# Maiskolben_THT.net
KiCad netlist of a schematic drawn in EAGLE
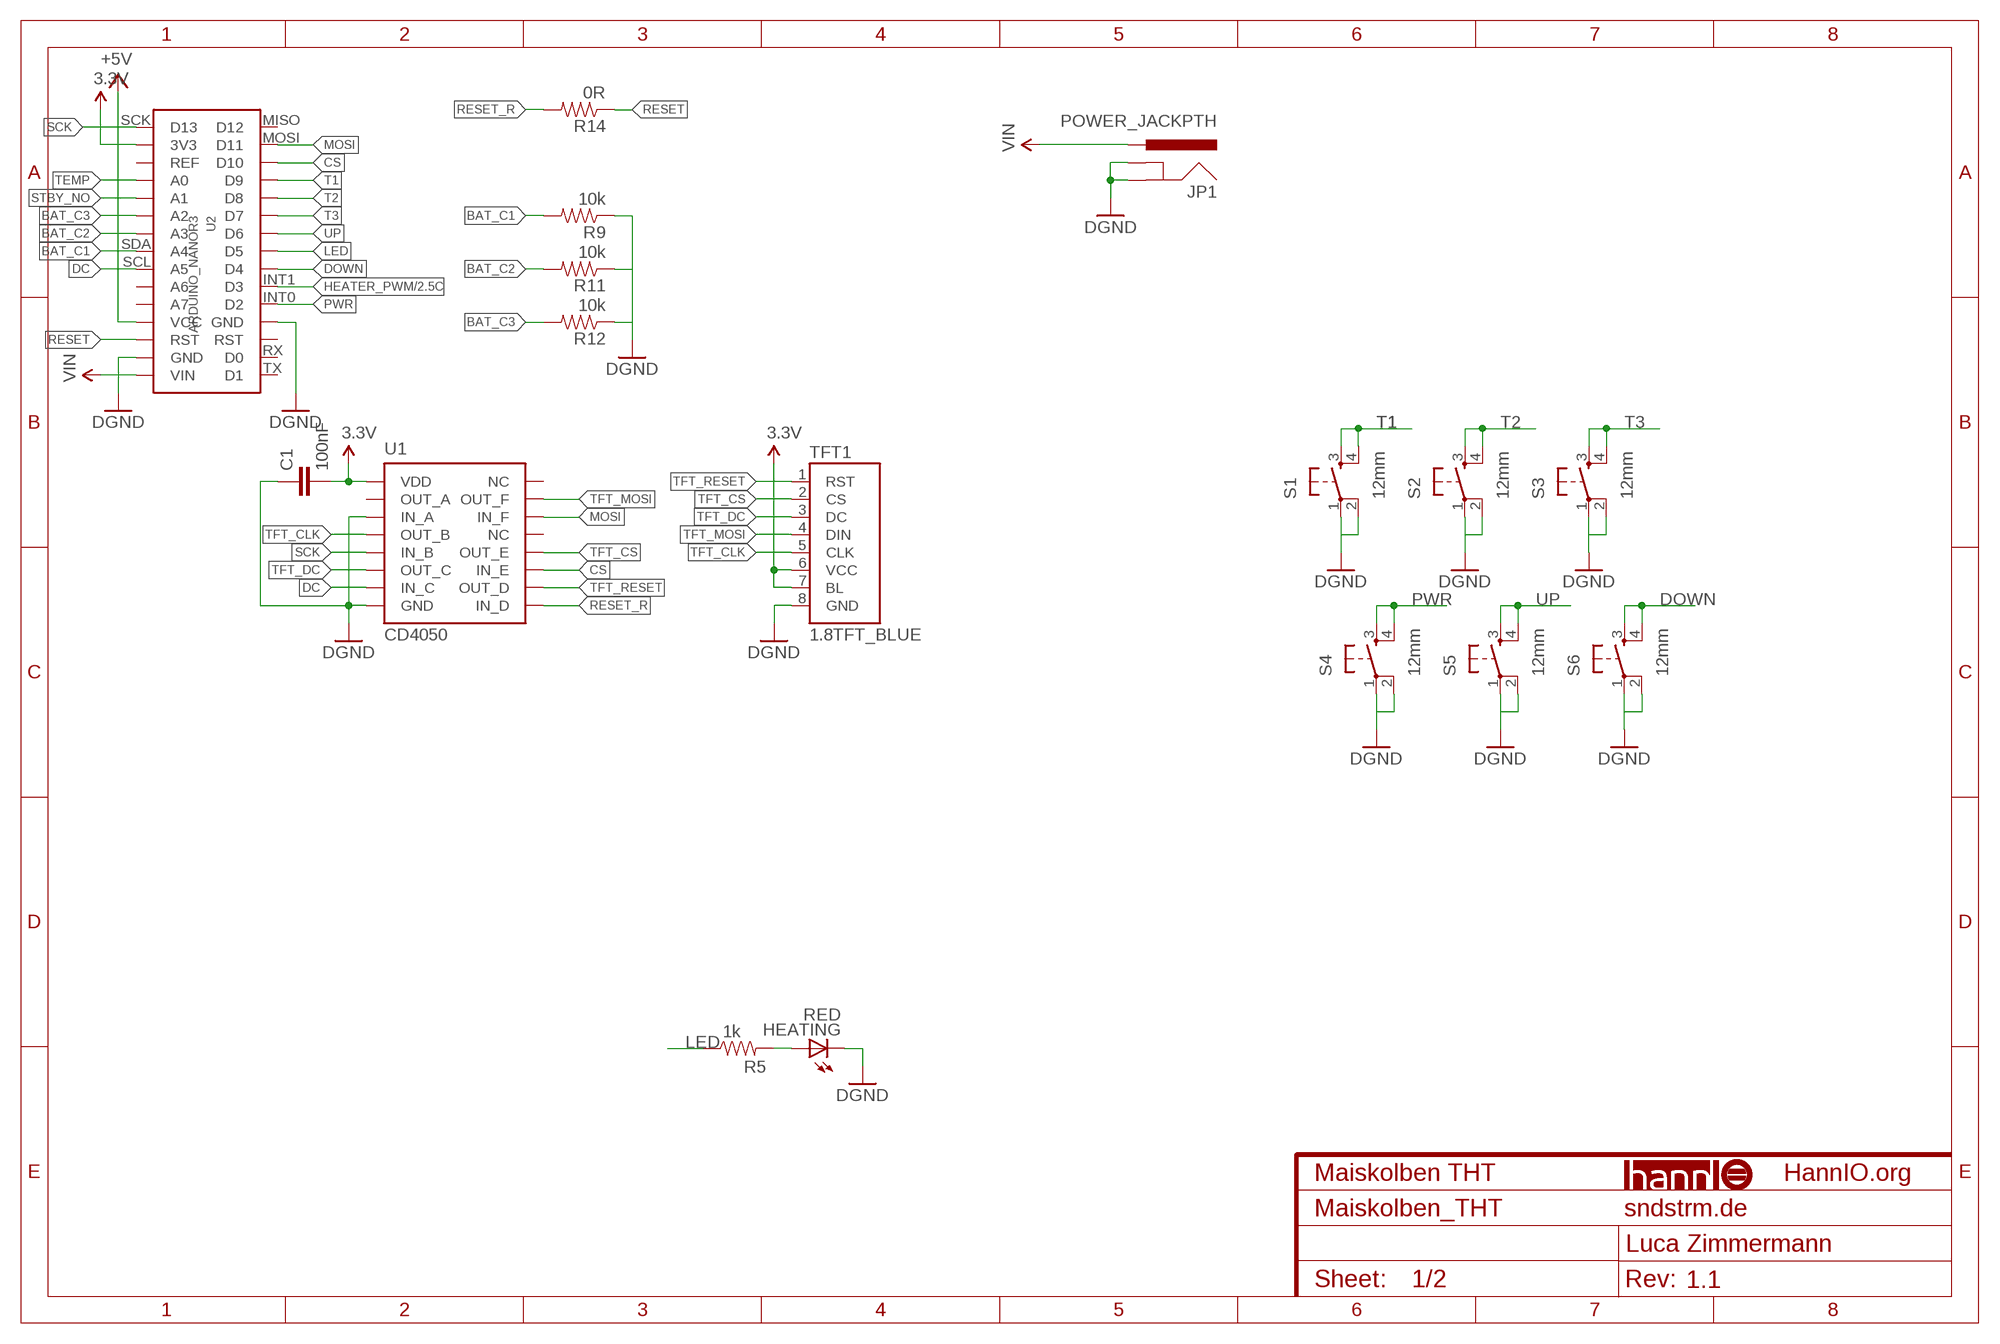
[diagram p0: schematic, sheet 1]
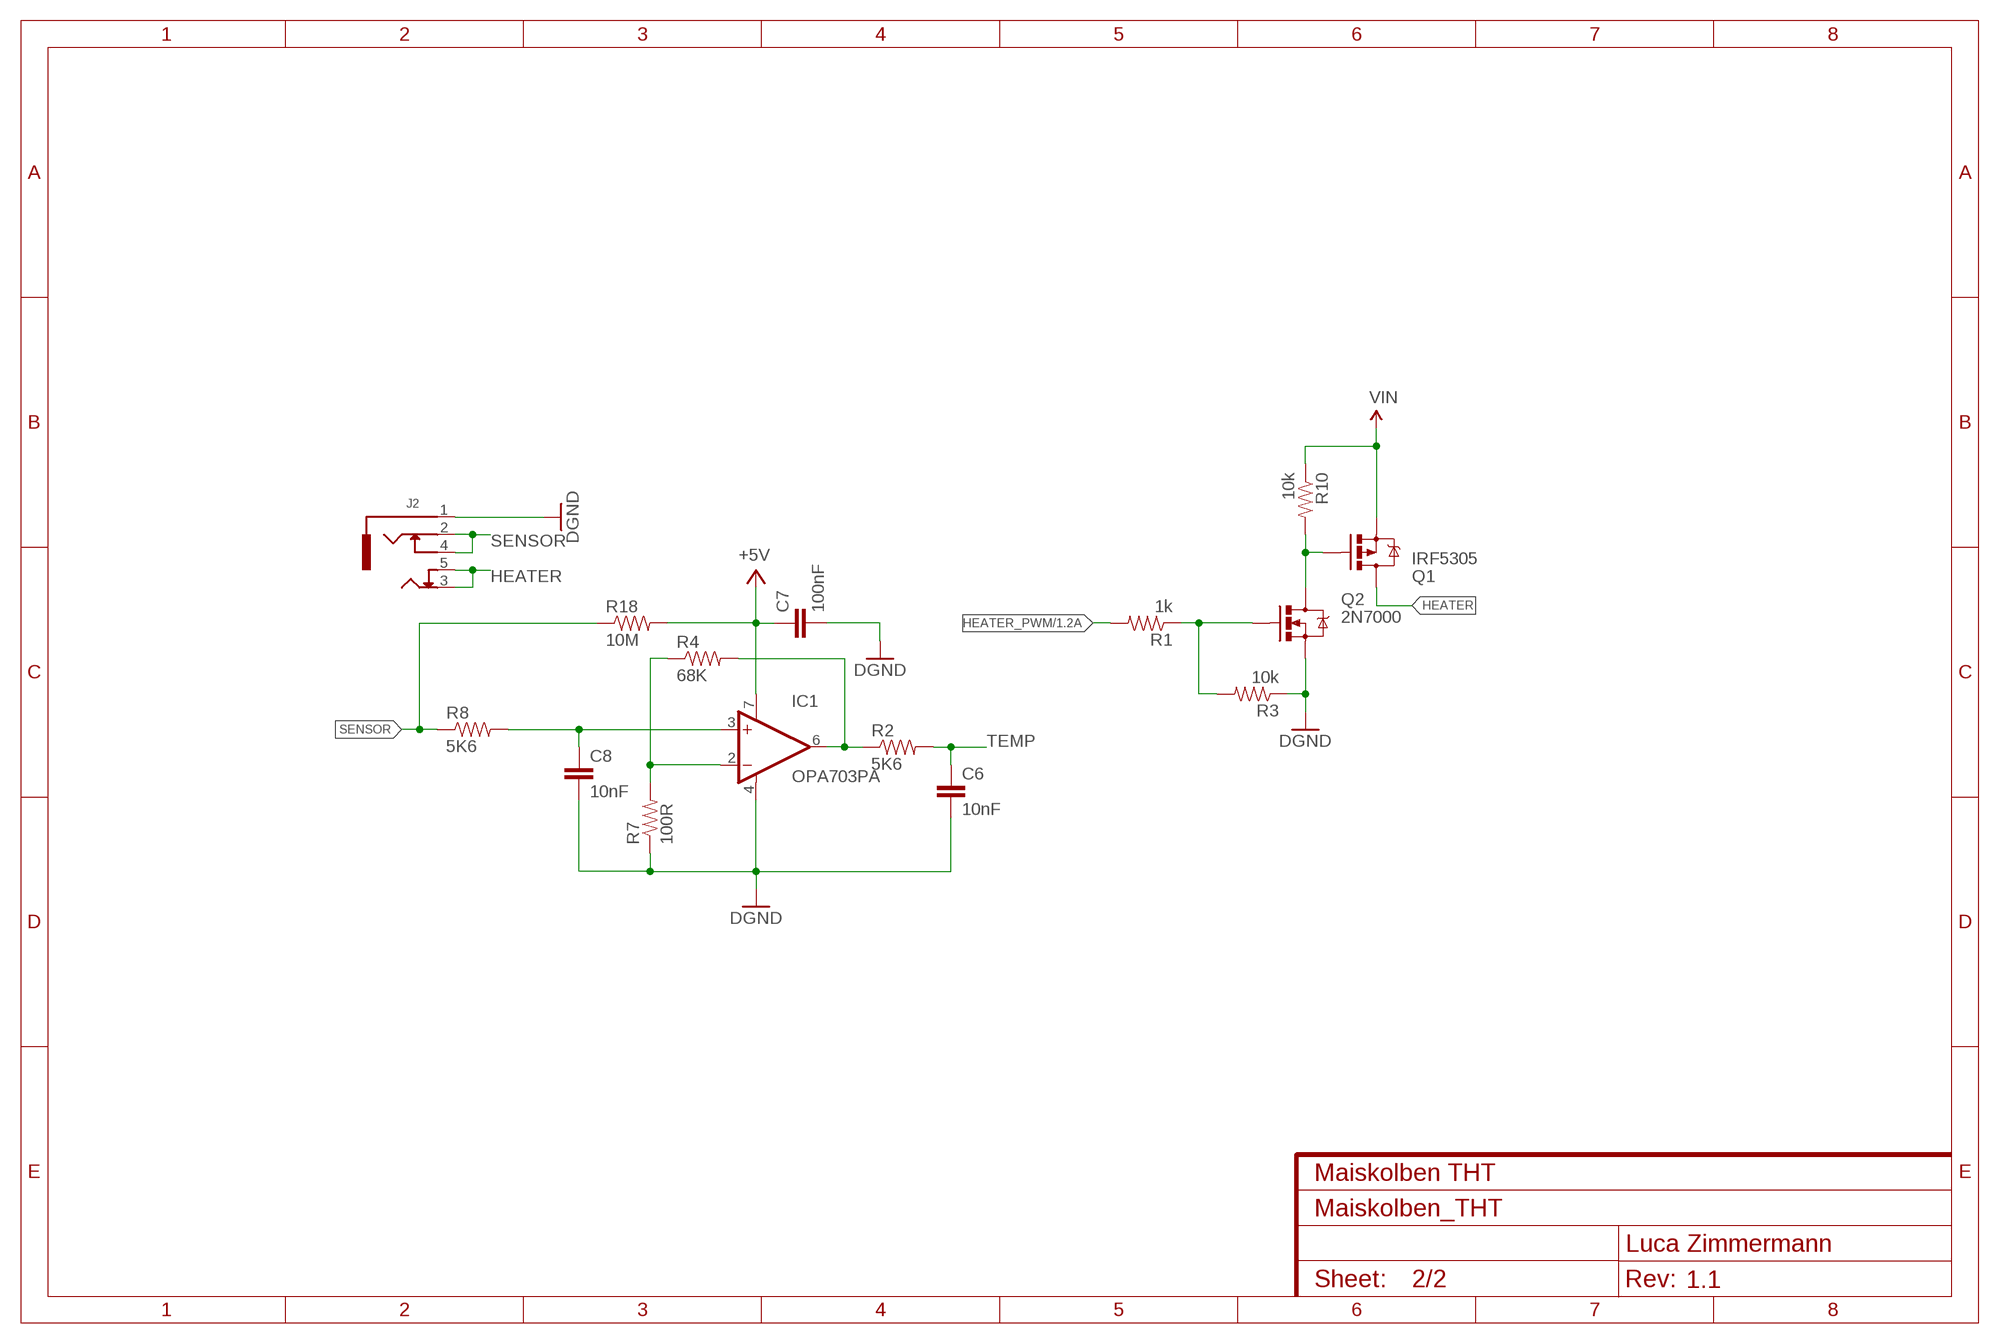
[diagram p1: schematic, sheet 2]

(export (version "E")
  (design (tool "Eeschema 10.0.6"))
  (components
    (comp (ref "C6")
      (value "10nF")
      (footprint "eagle-import:CAP-PTH-SMALLEZ")
      (libsource (lib "eagle-import") (part "CAPEZ"))
    )
    (comp (ref "C7")
      (value "100nF")
      (footprint "eagle-import:CAP-PTH-SMALLEZ")
      (libsource (lib "eagle-import") (part "CAPEZ"))
    )
    (comp (ref "C8")
      (value "10nF")
      (footprint "eagle-import:CAP-PTH-SMALLEZ")
      (libsource (lib "eagle-import") (part "CAPEZ"))
    )
    (comp (ref "IC1")
      (value "OPA703PA")
      (footprint "eagle-import:DIL08")
      (fields (field (name "MPN") "OPA340PA"))
      (libsource (lib "eagle-import") (part "OPA340P"))
    )
    (comp (ref "J2")
      (value "AUDIO_JACK_5PEBS_35")
      (footprint "eagle-import:EBS_35")
      (libsource (lib "eagle-import") (part "AUDIO_JACK_5PEBS_35"))
    )
    (comp (ref "Q1")
      (value "IRF5305")
      (footprint "eagle-import:TO220V")
      (libsource (lib "eagle-import") (part "MOSFET-PCHANNELFQP27P06"))
    )
    (comp (ref "Q2")
      (value "2N7000")
      (footprint "eagle-import:TO-92")
      (libsource (lib "eagle-import") (part "MOSFET-NCHANNEL2N7000"))
    )
    (comp (ref "R1")
      (value "1k")
      (footprint "eagle-import:AXIAL-0.3")
      (libsource (lib "eagle-import") (part "RESISTORAXIAL-0.3"))
    )
    (comp (ref "R2")
      (value "5K6")
      (footprint "eagle-import:AXIAL-0.3")
      (libsource (lib "eagle-import") (part "RESISTORAXIAL-0.3"))
    )
    (comp (ref "R3")
      (value "10k")
      (footprint "eagle-import:AXIAL-0.3")
      (libsource (lib "eagle-import") (part "RESISTORAXIAL-0.3"))
    )
    (comp (ref "R4")
      (value "68K")
      (footprint "eagle-import:AXIAL-0.3")
      (libsource (lib "eagle-import") (part "RESISTORAXIAL-0.3"))
    )
    (comp (ref "R7")
      (value "100R")
      (footprint "eagle-import:AXIAL-0.3")
      (libsource (lib "eagle-import") (part "RESISTORAXIAL-0.3"))
    )
    (comp (ref "R8")
      (value "5K6")
      (footprint "eagle-import:AXIAL-0.3")
      (libsource (lib "eagle-import") (part "RESISTORAXIAL-0.3"))
    )
    (comp (ref "R10")
      (value "10k")
      (footprint "eagle-import:AXIAL-0.3")
      (libsource (lib "eagle-import") (part "RESISTORAXIAL-0.3"))
    )
    (comp (ref "R18")
      (value "10M")
      (footprint "eagle-import:AXIAL-0.3")
      (libsource (lib "eagle-import") (part "RESISTORAXIAL-0.3"))
    )
    (comp (ref "C1")
      (value "100nF")
      (footprint "eagle-import:CAP-PTH-SMALLEZ")
      (libsource (lib "eagle-import") (part "CAPEZ"))
    )
    (comp (ref "HEATING")
      (value "RED")
      (footprint "eagle-import:LED5MM")
      (libsource (lib "eagle-import") (part "LED5MM"))
    )
    (comp (ref "JP1")
      (value "POWER_JACKPTH")
      (footprint "eagle-import:POWER_JACK_PTH")
      (libsource (lib "eagle-import") (part "POWER_JACKPTH"))
    )
    (comp (ref "R5")
      (value "1k")
      (footprint "eagle-import:AXIAL-0.3")
      (libsource (lib "eagle-import") (part "RESISTORAXIAL-0.3"))
    )
    (comp (ref "R9")
      (value "10k")
      (footprint "eagle-import:AXIAL-0.3")
      (libsource (lib "eagle-import") (part "RESISTORAXIAL-0.3"))
    )
    (comp (ref "R11")
      (value "10k")
      (footprint "eagle-import:AXIAL-0.3")
      (libsource (lib "eagle-import") (part "RESISTORAXIAL-0.3"))
    )
    (comp (ref "R12")
      (value "10k")
      (footprint "eagle-import:AXIAL-0.3")
      (libsource (lib "eagle-import") (part "RESISTORAXIAL-0.3"))
    )
    (comp (ref "R14")
      (value "0R")
      (footprint "eagle-import:AXIAL-0.3")
      (libsource (lib "eagle-import") (part "RESISTORAXIAL-0.3"))
    )
    (comp (ref "S1")
      (value "12mm")
      (footprint "eagle-import:TACTILE-PTH")
      (libsource (lib "eagle-import") (part "TAC_SWITCHPTH"))
    )
    (comp (ref "S2")
      (value "12mm")
      (footprint "eagle-import:TACTILE-PTH")
      (libsource (lib "eagle-import") (part "TAC_SWITCHPTH"))
    )
    (comp (ref "S3")
      (value "12mm")
      (footprint "eagle-import:TACTILE-PTH")
      (libsource (lib "eagle-import") (part "TAC_SWITCHPTH"))
    )
    (comp (ref "S4")
      (value "12mm")
      (footprint "eagle-import:TACTILE-PTH")
      (libsource (lib "eagle-import") (part "TAC_SWITCHPTH"))
    )
    (comp (ref "S5")
      (value "12mm")
      (footprint "eagle-import:TACTILE-PTH")
      (libsource (lib "eagle-import") (part "TAC_SWITCHPTH"))
    )
    (comp (ref "S6")
      (value "12mm")
      (footprint "eagle-import:TACTILE-PTH")
      (libsource (lib "eagle-import") (part "TAC_SWITCHPTH"))
    )
    (comp (ref "TFT1")
      (value "1.8TFT_BLUE")
      (footprint "eagle-import:1.8TFT_BLUE")
      (libsource (lib "eagle-import") (part "1.8TFT_BLUE"))
    )
    (comp (ref "U$1")
      (value "HANNIO_MEDIUM")
      (footprint "eagle-import:HANNIO_MEDIUM")
      (libsource (lib "eagle-import") (part "HANNIO_MEDIUM"))
    )
    (comp (ref "U1")
      (value "CD4050DIP16")
      (footprint "eagle-import:CD4050")
      (libsource (lib "eagle-import") (part "CD4050DIP16"))
    )
    (comp (ref "U2")
      (value "ARDUINO_NANOR3")
      (footprint "eagle-import:ARDUINO-NANO")
      (libsource (lib "eagle-import") (part "ARDUINO_NANOR3"))
    )
  )
  (nets
    (net (code "1") (name "+5V") (class "Default")
      (node (ref "C7") (pin "1") (pinfunction "1_1") (pintype "passive"))
      (node (ref "IC1") (pin "7") (pinfunction "V+_7") (pintype "power_in"))
      (node (ref "R18") (pin "P$2") (pinfunction "2_P$2") (pintype "passive"))
      (node (ref "U2") (pin "VCC") (pinfunction "VCC_VCC") (pintype "power_in"))
    )
    (net (code "2") (name "3.3V") (class "Default")
      (node (ref "C1") (pin "2") (pinfunction "2_2") (pintype "passive"))
      (node (ref "TFT1") (pin "6") (pinfunction "VCC_6") (pintype "power_in"))
      (node (ref "TFT1") (pin "7") (pinfunction "BL_7") (pintype "passive"))
      (node (ref "U1") (pin "VDD") (pinfunction "VDD_VDD") (pintype "power_in"))
      (node (ref "U2") (pin "3V3") (pinfunction "3V3_3V3") (pintype "power_in"))
    )
    (net (code "3") (name "BAT_C1") (class "Default")
      (node (ref "R9") (pin "P$2") (pinfunction "2_P$2") (pintype "passive"))
      (node (ref "U2") (pin "SDA") (pinfunction "A4_SDA") (pintype "bidirectional"))
    )
    (net (code "4") (name "BAT_C2") (class "Default")
      (node (ref "R11") (pin "P$2") (pinfunction "2_P$2") (pintype "passive"))
      (node (ref "U2") (pin "A3") (pinfunction "A3_A3") (pintype "bidirectional"))
    )
    (net (code "5") (name "BAT_C3") (class "Default")
      (node (ref "R12") (pin "P$2") (pinfunction "2_P$2") (pintype "passive"))
      (node (ref "U2") (pin "A2") (pinfunction "A2_A2") (pintype "bidirectional"))
    )
    (net (code "6") (name "CS") (class "Default")
      (node (ref "U1") (pin "IN_E") (pinfunction "IN_E_IN_E") (pintype "bidirectional"))
      (node (ref "U2") (pin "D10") (pinfunction "D10_D10") (pintype "bidirectional"))
    )
    (net (code "7") (name "DC") (class "Default")
      (node (ref "U1") (pin "IN_C") (pinfunction "IN_C_IN_C") (pintype "bidirectional"))
      (node (ref "U2") (pin "SCL") (pinfunction "A5_SCL") (pintype "bidirectional"))
    )
    (net (code "8") (name "DGND") (class "Default")
      (node (ref "C1") (pin "1") (pinfunction "1_1") (pintype "passive"))
      (node (ref "C6") (pin "2") (pinfunction "2_2") (pintype "passive"))
      (node (ref "C7") (pin "2") (pinfunction "2_2") (pintype "passive"))
      (node (ref "C8") (pin "2") (pinfunction "2_2") (pintype "passive"))
      (node (ref "HEATING") (pin "K") (pinfunction "C_K") (pintype "passive"))
      (node (ref "IC1") (pin "4") (pinfunction "V-_4") (pintype "power_in"))
      (node (ref "J2") (pin "1") (pinfunction "GND_1") (pintype "bidirectional"))
      (node (ref "JP1") (pin "GND") (pinfunction "GND_GND") (pintype "bidirectional"))
      (node (ref "JP1") (pin "GNDBREAK") (pinfunction "GNDBREAK_GNDBREAK") (pintype "bidirectional"))
      (node (ref "Q2") (pin "1") (pinfunction "S_1") (pintype "passive"))
      (node (ref "R11") (pin "P$1") (pinfunction "1_P$1") (pintype "passive"))
      (node (ref "R12") (pin "P$1") (pinfunction "1_P$1") (pintype "passive"))
      (node (ref "R3") (pin "P$1") (pinfunction "1_P$1") (pintype "passive"))
      (node (ref "R7") (pin "P$1") (pinfunction "1_P$1") (pintype "passive"))
      (node (ref "R9") (pin "P$1") (pinfunction "1_P$1") (pintype "passive"))
      (node (ref "S1") (pin "1") (pinfunction "1_1") (pintype "passive"))
      (node (ref "S1") (pin "2") (pinfunction "2_2") (pintype "passive"))
      (node (ref "S2") (pin "1") (pinfunction "1_1") (pintype "passive"))
      (node (ref "S2") (pin "2") (pinfunction "2_2") (pintype "passive"))
      (node (ref "S3") (pin "1") (pinfunction "1_1") (pintype "passive"))
      (node (ref "S3") (pin "2") (pinfunction "2_2") (pintype "passive"))
      (node (ref "S4") (pin "1") (pinfunction "1_1") (pintype "passive"))
      (node (ref "S4") (pin "2") (pinfunction "2_2") (pintype "passive"))
      (node (ref "S5") (pin "1") (pinfunction "1_1") (pintype "passive"))
      (node (ref "S5") (pin "2") (pinfunction "2_2") (pintype "passive"))
      (node (ref "S6") (pin "1") (pinfunction "1_1") (pintype "passive"))
      (node (ref "S6") (pin "2") (pinfunction "2_2") (pintype "passive"))
      (node (ref "TFT1") (pin "8") (pinfunction "GND_8") (pintype "power_in"))
      (node (ref "U1") (pin "GND") (pinfunction "GND_GND") (pintype "power_in"))
      (node (ref "U1") (pin "IN_A") (pinfunction "IN_A_IN_A") (pintype "bidirectional"))
      (node (ref "U2") (pin "GND@1") (pinfunction "GND_GND@1") (pintype "power_in"))
      (node (ref "U2") (pin "GND@2") (pinfunction "GND_GND@2") (pintype "power_in"))
    )
    (net (code "9") (name "DOWN") (class "Default")
      (node (ref "S6") (pin "3") (pinfunction "3_3") (pintype "passive"))
      (node (ref "S6") (pin "4") (pinfunction "4_4") (pintype "passive"))
      (node (ref "U2") (pin "D4") (pinfunction "D4_D4") (pintype "bidirectional"))
    )
    (net (code "10") (name "HEATER") (class "Default")
      (node (ref "J2") (pin "3") (pinfunction "TIP_3") (pintype "bidirectional"))
      (node (ref "J2") (pin "5") (pinfunction "TIP_NC_5") (pintype "bidirectional"))
      (node (ref "Q1") (pin "2") (pinfunction "D_2") (pintype "passive"))
    )
    (net (code "11") (name "HEATER_PWM") (class "Default")
      (node (ref "R1") (pin "P$2") (pinfunction "2_P$2") (pintype "passive"))
      (node (ref "U2") (pin "INT1") (pinfunction "D3_INT1") (pintype "bidirectional"))
    )
    (net (code "12") (name "LED") (class "Default")
      (node (ref "R5") (pin "P$1") (pinfunction "1_P$1") (pintype "passive"))
      (node (ref "U2") (pin "D5") (pinfunction "D5_D5") (pintype "bidirectional"))
    )
    (net (code "13") (name "MOSI") (class "Default")
      (node (ref "U1") (pin "IN_F") (pinfunction "IN_F_IN_F") (pintype "bidirectional"))
      (node (ref "U2") (pin "MOSI") (pinfunction "D11_MOSI") (pintype "bidirectional"))
    )
    (net (code "14") (name "Net-(IC1-+IN)") (class "Default")
      (node (ref "C8") (pin "1") (pinfunction "1_1") (pintype "passive"))
      (node (ref "IC1") (pin "3") (pinfunction "+IN_3") (pintype "input"))
      (node (ref "R8") (pin "P$2") (pinfunction "2_P$2") (pintype "passive"))
    )
    (net (code "15") (name "Net-(IC1--IN)") (class "Default")
      (node (ref "IC1") (pin "2") (pinfunction "-IN_2") (pintype "input"))
      (node (ref "R4") (pin "P$1") (pinfunction "1_P$1") (pintype "passive"))
      (node (ref "R7") (pin "P$2") (pinfunction "2_P$2") (pintype "passive"))
    )
    (net (code "16") (name "Net-(IC1-OUT)") (class "Default")
      (node (ref "IC1") (pin "6") (pinfunction "OUT_6") (pintype "output"))
      (node (ref "R2") (pin "P$1") (pinfunction "1_P$1") (pintype "passive"))
      (node (ref "R4") (pin "P$2") (pinfunction "2_P$2") (pintype "passive"))
    )
    (net (code "17") (name "Net-(Q1-G)") (class "Default")
      (node (ref "Q1") (pin "1") (pinfunction "G_1") (pintype "passive"))
      (node (ref "Q2") (pin "3") (pinfunction "D_3") (pintype "passive"))
      (node (ref "R10") (pin "P$2") (pinfunction "2_P$2") (pintype "passive"))
    )
    (net (code "18") (name "Net-(Q2-G)") (class "Default")
      (node (ref "Q2") (pin "2") (pinfunction "G_2") (pintype "passive"))
      (node (ref "R1") (pin "P$1") (pinfunction "1_P$1") (pintype "passive"))
      (node (ref "R3") (pin "P$2") (pinfunction "2_P$2") (pintype "passive"))
    )
    (net (code "19") (name "Net-(R5-2)") (class "Default")
      (node (ref "HEATING") (pin "A") (pinfunction "A_A") (pintype "passive"))
      (node (ref "R5") (pin "P$2") (pinfunction "2_P$2") (pintype "passive"))
    )
    (net (code "20") (name "PWR") (class "Default")
      (node (ref "S4") (pin "3") (pinfunction "3_3") (pintype "passive"))
      (node (ref "S4") (pin "4") (pinfunction "4_4") (pintype "passive"))
      (node (ref "U2") (pin "INT0") (pinfunction "D2_INT0") (pintype "bidirectional"))
    )
    (net (code "21") (name "RESET") (class "Default")
      (node (ref "R14") (pin "P$1") (pinfunction "1_P$1") (pintype "passive"))
      (node (ref "U2") (pin "RST@2") (pinfunction "RST_RST@2") (pintype "bidirectional"))
    )
    (net (code "22") (name "RESET_R") (class "Default")
      (node (ref "R14") (pin "P$2") (pinfunction "2_P$2") (pintype "passive"))
      (node (ref "U1") (pin "IN_D") (pinfunction "IN_D_IN_D") (pintype "bidirectional"))
    )
    (net (code "23") (name "SCK") (class "Default")
      (node (ref "U1") (pin "IN_B") (pinfunction "IN_B_IN_B") (pintype "bidirectional"))
      (node (ref "U2") (pin "SCK") (pinfunction "D13_SCK") (pintype "bidirectional"))
    )
    (net (code "24") (name "SENSOR") (class "Default")
      (node (ref "J2") (pin "2") (pinfunction "RING_2") (pintype "bidirectional"))
      (node (ref "J2") (pin "4") (pinfunction "RING_NC_4") (pintype "bidirectional"))
      (node (ref "R18") (pin "P$1") (pinfunction "1_P$1") (pintype "passive"))
      (node (ref "R8") (pin "P$1") (pinfunction "1_P$1") (pintype "passive"))
    )
    (net (code "25") (name "STBY_NO") (class "Default")
      (node (ref "U2") (pin "A1") (pinfunction "A1_A1") (pintype "bidirectional"))
    )
    (net (code "26") (name "T1") (class "Default")
      (node (ref "S1") (pin "3") (pinfunction "3_3") (pintype "passive"))
      (node (ref "S1") (pin "4") (pinfunction "4_4") (pintype "passive"))
      (node (ref "U2") (pin "D9") (pinfunction "D9_D9") (pintype "bidirectional"))
    )
    (net (code "27") (name "T2") (class "Default")
      (node (ref "S2") (pin "3") (pinfunction "3_3") (pintype "passive"))
      (node (ref "S2") (pin "4") (pinfunction "4_4") (pintype "passive"))
      (node (ref "U2") (pin "D8") (pinfunction "D8_D8") (pintype "bidirectional"))
    )
    (net (code "28") (name "T3") (class "Default")
      (node (ref "S3") (pin "3") (pinfunction "3_3") (pintype "passive"))
      (node (ref "S3") (pin "4") (pinfunction "4_4") (pintype "passive"))
      (node (ref "U2") (pin "D7") (pinfunction "D7_D7") (pintype "bidirectional"))
    )
    (net (code "29") (name "TEMP") (class "Default")
      (node (ref "C6") (pin "1") (pinfunction "1_1") (pintype "passive"))
      (node (ref "R2") (pin "P$2") (pinfunction "2_P$2") (pintype "passive"))
      (node (ref "U2") (pin "A0") (pinfunction "A0_A0") (pintype "bidirectional"))
    )
    (net (code "30") (name "TFT_CLK") (class "Default")
      (node (ref "TFT1") (pin "5") (pinfunction "CLK_5") (pintype "input"))
      (node (ref "U1") (pin "OUT_B") (pinfunction "OUT_B_OUT_B") (pintype "bidirectional"))
    )
    (net (code "31") (name "TFT_CS") (class "Default")
      (node (ref "TFT1") (pin "2") (pinfunction "CS_2") (pintype "input"))
      (node (ref "U1") (pin "OUT_E") (pinfunction "OUT_E_OUT_E") (pintype "bidirectional"))
    )
    (net (code "32") (name "TFT_DC") (class "Default")
      (node (ref "TFT1") (pin "3") (pinfunction "DC_3") (pintype "input"))
      (node (ref "U1") (pin "OUT_C") (pinfunction "OUT_C_OUT_C") (pintype "bidirectional"))
    )
    (net (code "33") (name "TFT_MOSI") (class "Default")
      (node (ref "TFT1") (pin "4") (pinfunction "DIN_4") (pintype "input"))
      (node (ref "U1") (pin "OUT_F") (pinfunction "OUT_F_OUT_F") (pintype "bidirectional"))
    )
    (net (code "34") (name "TFT_RESET") (class "Default")
      (node (ref "TFT1") (pin "1") (pinfunction "RST_1") (pintype "input"))
      (node (ref "U1") (pin "OUT_D") (pinfunction "OUT_D_OUT_D") (pintype "bidirectional"))
    )
    (net (code "35") (name "UP") (class "Default")
      (node (ref "S5") (pin "3") (pinfunction "3_3") (pintype "passive"))
      (node (ref "S5") (pin "4") (pinfunction "4_4") (pintype "passive"))
      (node (ref "U2") (pin "D6") (pinfunction "D6_D6") (pintype "bidirectional"))
    )
    (net (code "36") (name "VIN") (class "Default")
      (node (ref "JP1") (pin "PWR") (pinfunction "PWR_PWR") (pintype "bidirectional"))
      (node (ref "Q1") (pin "3") (pinfunction "S_3") (pintype "passive"))
      (node (ref "R10") (pin "P$1") (pinfunction "1_P$1") (pintype "passive"))
      (node (ref "U2") (pin "VIN") (pinfunction "VIN_VIN") (pintype "power_in"))
    )
    (net (code "37") (name "unconnected-(U1-NC-PadNC@1)") (class "Default")
      (node (ref "U1") (pin "NC@1") (pinfunction "NC_NC@1") (pintype "no_connect"))
    )
    (net (code "38") (name "unconnected-(U1-NC-PadNC@2)") (class "Default")
      (node (ref "U1") (pin "NC@2") (pinfunction "NC_NC@2") (pintype "no_connect"))
    )
    (net (code "39") (name "unconnected-(U1-PadOUT_A)") (class "Default")
      (node (ref "U1") (pin "OUT_A") (pinfunction "OUT_A_OUT_A") (pintype "bidirectional"))
    )
    (net (code "40") (name "unconnected-(U2-D0-PadRX)") (class "Default")
      (node (ref "U2") (pin "RX") (pinfunction "D0_RX") (pintype "bidirectional"))
    )
    (net (code "41") (name "unconnected-(U2-D1-PadTX)") (class "Default")
      (node (ref "U2") (pin "TX") (pinfunction "D1_TX") (pintype "bidirectional"))
    )
    (net (code "42") (name "unconnected-(U2-D12-PadMISO)") (class "Default")
      (node (ref "U2") (pin "MISO") (pinfunction "D12_MISO") (pintype "bidirectional"))
    )
    (net (code "43") (name "unconnected-(U2-PadA6)") (class "Default")
      (node (ref "U2") (pin "A6") (pinfunction "A6_A6") (pintype "bidirectional"))
    )
    (net (code "44") (name "unconnected-(U2-PadA7)") (class "Default")
      (node (ref "U2") (pin "A7") (pinfunction "A7_A7") (pintype "bidirectional"))
    )
    (net (code "45") (name "unconnected-(U2-PadREF)") (class "Default")
      (node (ref "U2") (pin "REF") (pinfunction "REF_REF") (pintype "bidirectional"))
    )
    (net (code "46") (name "unconnected-(U2-RST-PadRST@1)") (class "Default")
      (node (ref "U2") (pin "RST@1") (pinfunction "RST_RST@1") (pintype "bidirectional"))
    )
  )
)
